# basic_board.net
KiCad netlist of a schematic drawn in EAGLE
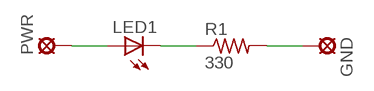
[diagram p0: schematic, sheet 1]

(export (version "E")
  (design (tool "Eeschema 10.0.6"))
  (components
    (comp (ref "GND")
      (value "LSP11")
      (footprint "eagle-import:LSP11")
      (libsource (lib "eagle-import") (part "LSP11"))
    )
    (comp (ref "LED1")
      (value "LED3MM")
      (footprint "eagle-import:LED3MM")
      (libsource (lib "eagle-import") (part "LED3MM"))
    )
    (comp (ref "PWR")
      (value "LSP11")
      (footprint "eagle-import:LSP11")
      (libsource (lib "eagle-import") (part "LSP11"))
    )
    (comp (ref "R1")
      (value "330")
      (footprint "eagle-import:0207_7")
      (libsource (lib "eagle-import") (part "R-US_0207/7"))
    )
  )
  (nets
    (net (code "1") (name "Net-(GND-PadMP)") (class "Default")
      (node (ref "GND") (pin "MP") (pinfunction "MP_MP") (pintype "passive"))
      (node (ref "R1") (pin "2") (pinfunction "2_2") (pintype "passive"))
    )
    (net (code "2") (name "Net-(LED1-C)") (class "Default")
      (node (ref "LED1") (pin "K") (pinfunction "C_K") (pintype "passive"))
      (node (ref "R1") (pin "1") (pinfunction "1_1") (pintype "passive"))
    )
    (net (code "3") (name "Net-(LED1-PadA)") (class "Default")
      (node (ref "LED1") (pin "A") (pinfunction "A_A") (pintype "passive"))
      (node (ref "PWR") (pin "MP") (pinfunction "MP_MP") (pintype "passive"))
    )
  )
)
